# pmic.net
KiCad netlist of a schematic drawn in Altium Designer
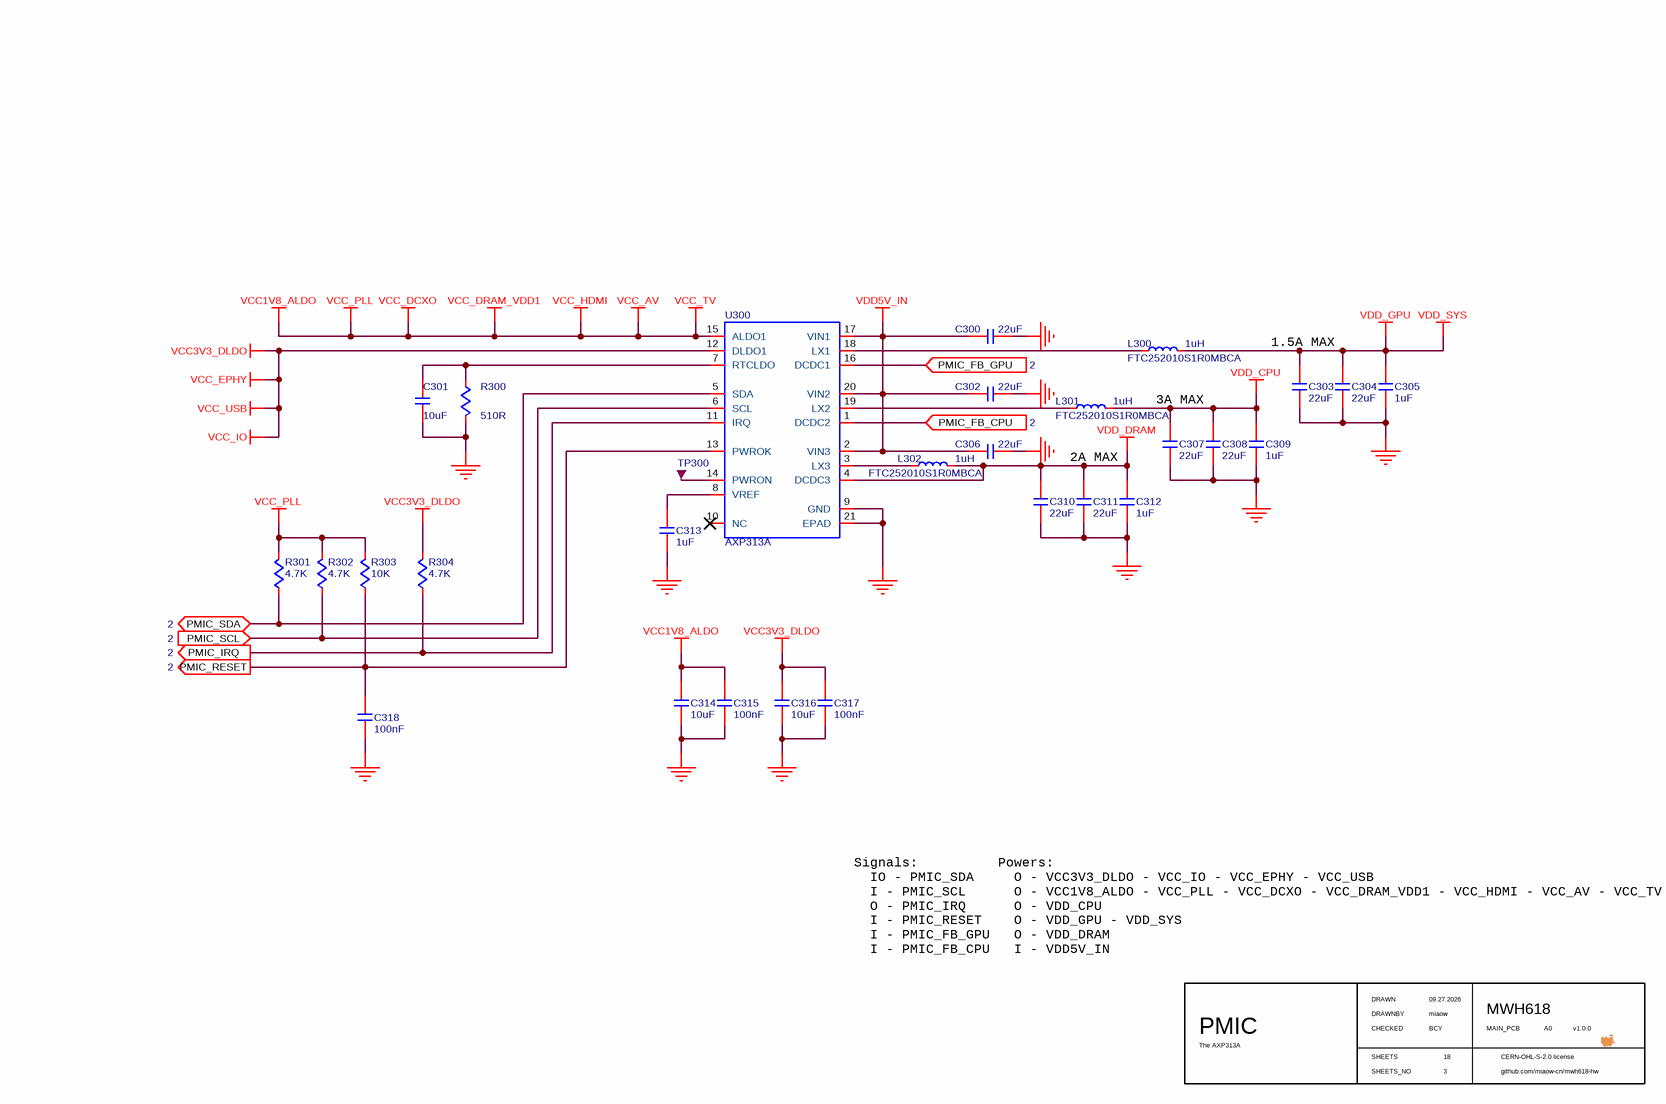
[diagram p0: pmic.schdoc]

(export (version "E")
  (design (tool "Eeschema 10.0.6"))
  (components
    (comp (ref "C300")
      (value "22uF")
      (footprint "mw:C0603")
      (fields (field (name "VOLTAGE") "10V") (field (name "Comment") "C-NOMO"))
      (libsource (lib "mw") (part "C-NOMO"))
    )
    (comp (ref "C301")
      (value "10uF")
      (footprint "mw:C0402")
      (fields (field (name "VOLTAGE") "6.3V") (field (name "Comment") "C-NOMO"))
      (libsource (lib "mw") (part "C-NOMO"))
    )
    (comp (ref "C302")
      (value "22uF")
      (footprint "mw:C0603")
      (fields (field (name "VOLTAGE") "10V") (field (name "Comment") "C-NOMO"))
      (libsource (lib "mw") (part "C-NOMO"))
    )
    (comp (ref "C303")
      (value "22uF")
      (footprint "mw:C0603")
      (fields (field (name "VOLTAGE") "10V") (field (name "Comment") "C-NOMO"))
      (libsource (lib "mw") (part "C-NOMO"))
    )
    (comp (ref "C304")
      (value "22uF")
      (footprint "mw:C0603")
      (fields (field (name "VOLTAGE") "10V") (field (name "Comment") "C-NOMO"))
      (libsource (lib "mw") (part "C-NOMO"))
    )
    (comp (ref "C305")
      (value "1uF")
      (footprint "mw:C0402")
      (fields (field (name "VOLTAGE") "25V") (field (name "Comment") "C-NOMO"))
      (libsource (lib "mw") (part "C-NOMO"))
    )
    (comp (ref "C306")
      (value "22uF")
      (footprint "mw:C0603")
      (fields (field (name "VOLTAGE") "10V") (field (name "Comment") "C-NOMO"))
      (libsource (lib "mw") (part "C-NOMO"))
    )
    (comp (ref "C307")
      (value "22uF")
      (footprint "mw:C0603")
      (fields (field (name "VOLTAGE") "10V") (field (name "Comment") "C-NOMO"))
      (libsource (lib "mw") (part "C-NOMO"))
    )
    (comp (ref "C308")
      (value "22uF")
      (footprint "mw:C0603")
      (fields (field (name "VOLTAGE") "10V") (field (name "Comment") "C-NOMO"))
      (libsource (lib "mw") (part "C-NOMO"))
    )
    (comp (ref "C309")
      (value "1uF")
      (footprint "mw:C0402")
      (fields (field (name "VOLTAGE") "25V") (field (name "Comment") "C-NOMO"))
      (libsource (lib "mw") (part "C-NOMO"))
    )
    (comp (ref "C310")
      (value "22uF")
      (footprint "mw:C0603")
      (fields (field (name "VOLTAGE") "10V") (field (name "Comment") "C-NOMO"))
      (libsource (lib "mw") (part "C-NOMO"))
    )
    (comp (ref "C311")
      (value "22uF")
      (footprint "mw:C0603")
      (fields (field (name "VOLTAGE") "10V") (field (name "Comment") "C-NOMO"))
      (libsource (lib "mw") (part "C-NOMO"))
    )
    (comp (ref "C312")
      (value "1uF")
      (footprint "mw:C0402")
      (fields (field (name "VOLTAGE") "25V") (field (name "Comment") "C-NOMO"))
      (libsource (lib "mw") (part "C-NOMO"))
    )
    (comp (ref "C313")
      (value "1uF")
      (footprint "mw:C0402")
      (fields (field (name "VOLTAGE") "25V") (field (name "Comment") "C-NOMO"))
      (libsource (lib "mw") (part "C-NOMO"))
    )
    (comp (ref "C314")
      (value "10uF")
      (footprint "mw:C0402")
      (fields (field (name "VOLTAGE") "6.3V") (field (name "Comment") "C-NOMO"))
      (libsource (lib "mw") (part "C-NOMO"))
    )
    (comp (ref "C315")
      (value "100nF")
      (footprint "mw:C0402")
      (fields (field (name "VOLTAGE") "50V") (field (name "Comment") "C-NOMO"))
      (libsource (lib "mw") (part "C-NOMO"))
    )
    (comp (ref "C316")
      (value "10uF")
      (footprint "mw:C0402")
      (fields (field (name "VOLTAGE") "6.3V") (field (name "Comment") "C-NOMO"))
      (libsource (lib "mw") (part "C-NOMO"))
    )
    (comp (ref "C317")
      (value "100nF")
      (footprint "mw:C0402")
      (fields (field (name "VOLTAGE") "50V") (field (name "Comment") "C-NOMO"))
      (libsource (lib "mw") (part "C-NOMO"))
    )
    (comp (ref "C318")
      (value "100nF")
      (footprint "mw:C0402")
      (fields (field (name "VOLTAGE") "50V") (field (name "Comment") "C-NOMO"))
      (libsource (lib "mw") (part "C-NOMO"))
    )
    (comp (ref "L300")
      (value "FTC252010S1R0MBCA")
      (footprint "mw:FTC252010")
      (fields (field (name "ALTIUM_VALUE") "1uH") (field (name "PUBLISHER") "Altium Limited"))
      (libsource (lib "mw") (part "L"))
    )
    (comp (ref "L301")
      (value "FTC252010S1R0MBCA")
      (footprint "mw:FTC252010")
      (fields (field (name "ALTIUM_VALUE") "1uH") (field (name "PUBLISHER") "Altium Limited"))
      (libsource (lib "mw") (part "L"))
    )
    (comp (ref "L302")
      (value "FTC252010S1R0MBCA")
      (footprint "mw:FTC252010")
      (fields (field (name "ALTIUM_VALUE") "1uH") (field (name "PUBLISHER") "Altium Limited"))
      (libsource (lib "mw") (part "L"))
    )
    (comp (ref "R300")
      (value "510R")
      (footprint "mw:R0402")
      (fields (field (name "Comment") "R"))
      (libsource (lib "mw") (part "R"))
    )
    (comp (ref "R301")
      (value "4.7K")
      (footprint "mw:R0402")
      (fields (field (name "Comment") "R"))
      (libsource (lib "mw") (part "R"))
    )
    (comp (ref "R302")
      (value "4.7K")
      (footprint "mw:R0402")
      (fields (field (name "Comment") "R"))
      (libsource (lib "mw") (part "R"))
    )
    (comp (ref "R303")
      (value "10K")
      (footprint "mw:R0402")
      (fields (field (name "Comment") "R"))
      (libsource (lib "mw") (part "R"))
    )
    (comp (ref "R304")
      (value "4.7K")
      (footprint "mw:R0402")
      (fields (field (name "Comment") "R"))
      (libsource (lib "mw") (part "R"))
    )
    (comp (ref "TP300") (value "TP") (footprint "mw:TP") (libsource (lib "mw") (part "TP")))
    (comp (ref "U300")
      (value "AXP313A")
      (footprint "mw:AXP313A")
      (description "PMIC")
      (libsource (lib "mw") (part "AXP313A"))
    )
  )
  (nets
    (net (code "1") (name "/PMIC_FB_CPU") (class "Default")
      (node (ref "U300") (pin "1") (pinfunction "DCDC2_1") (pintype "passive"))
    )
    (net (code "2") (name "/PMIC_FB_GPU") (class "Default")
      (node (ref "U300") (pin "16") (pinfunction "DCDC1_16") (pintype "passive"))
    )
    (net (code "3") (name "/PMIC_IRQ") (class "Default")
      (node (ref "R304") (pin "2") (pinfunction "2_2") (pintype "passive"))
      (node (ref "U300") (pin "11") (pinfunction "IRQ_11") (pintype "passive"))
    )
    (net (code "4") (name "/PMIC_RESET") (class "Default")
      (node (ref "C318") (pin "1") (pinfunction "1_1") (pintype "passive"))
      (node (ref "R303") (pin "2") (pinfunction "2_2") (pintype "passive"))
      (node (ref "U300") (pin "13") (pinfunction "PWROK_13") (pintype "passive"))
    )
    (net (code "5") (name "/PMIC_SCL") (class "Default")
      (node (ref "R302") (pin "2") (pinfunction "2_2") (pintype "passive"))
      (node (ref "U300") (pin "6") (pinfunction "SCL_6") (pintype "passive"))
    )
    (net (code "6") (name "/PMIC_SDA") (class "Default")
      (node (ref "R301") (pin "2") (pinfunction "2_2") (pintype "passive"))
      (node (ref "U300") (pin "5") (pinfunction "SDA_5") (pintype "passive"))
    )
    (net (code "7") (name "GND") (class "Default")
      (node (ref "C300") (pin "2") (pinfunction "2_2") (pintype "passive"))
      (node (ref "C301") (pin "2") (pinfunction "2_2") (pintype "passive"))
      (node (ref "C302") (pin "2") (pinfunction "2_2") (pintype "passive"))
      (node (ref "C303") (pin "1") (pinfunction "1_1") (pintype "passive"))
      (node (ref "C304") (pin "1") (pinfunction "1_1") (pintype "passive"))
      (node (ref "C305") (pin "1") (pinfunction "1_1") (pintype "passive"))
      (node (ref "C306") (pin "2") (pinfunction "2_2") (pintype "passive"))
      (node (ref "C307") (pin "1") (pinfunction "1_1") (pintype "passive"))
      (node (ref "C308") (pin "1") (pinfunction "1_1") (pintype "passive"))
      (node (ref "C309") (pin "1") (pinfunction "1_1") (pintype "passive"))
      (node (ref "C310") (pin "1") (pinfunction "1_1") (pintype "passive"))
      (node (ref "C311") (pin "1") (pinfunction "1_1") (pintype "passive"))
      (node (ref "C312") (pin "1") (pinfunction "1_1") (pintype "passive"))
      (node (ref "C313") (pin "2") (pinfunction "2_2") (pintype "passive"))
      (node (ref "C314") (pin "2") (pinfunction "2_2") (pintype "passive"))
      (node (ref "C315") (pin "2") (pinfunction "2_2") (pintype "passive"))
      (node (ref "C316") (pin "2") (pinfunction "2_2") (pintype "passive"))
      (node (ref "C317") (pin "2") (pinfunction "2_2") (pintype "passive"))
      (node (ref "C318") (pin "2") (pinfunction "2_2") (pintype "passive"))
      (node (ref "R300") (pin "1") (pinfunction "1_1") (pintype "passive"))
      (node (ref "U300") (pin "21") (pinfunction "EPAD_21") (pintype "passive"))
      (node (ref "U300") (pin "9") (pinfunction "GND_9") (pintype "passive"))
    )
    (net (code "8") (name "Net-(U300-LX1)") (class "Default")
      (node (ref "L300") (pin "1") (pinfunction "1_1") (pintype "passive"))
      (node (ref "U300") (pin "18") (pinfunction "LX1_18") (pintype "passive"))
    )
    (net (code "9") (name "Net-(U300-LX2)") (class "Default")
      (node (ref "L301") (pin "1") (pinfunction "1_1") (pintype "passive"))
      (node (ref "U300") (pin "19") (pinfunction "LX2_19") (pintype "passive"))
    )
    (net (code "10") (name "Net-(U300-LX3)") (class "Default")
      (node (ref "L302") (pin "1") (pinfunction "1_1") (pintype "passive"))
      (node (ref "U300") (pin "3") (pinfunction "LX3_3") (pintype "passive"))
    )
    (net (code "11") (name "Net-(U300-PWRON)") (class "Default")
      (node (ref "TP300") (pin "0") (pintype "passive"))
      (node (ref "U300") (pin "14") (pinfunction "PWRON_14") (pintype "passive"))
    )
    (net (code "12") (name "Net-(U300-RTCLDO)") (class "Default")
      (node (ref "C301") (pin "1") (pinfunction "1_1") (pintype "passive"))
      (node (ref "R300") (pin "2") (pinfunction "2_2") (pintype "passive"))
      (node (ref "U300") (pin "7") (pinfunction "RTCLDO_7") (pintype "passive"))
    )
    (net (code "13") (name "Net-(U300-VREF)") (class "Default")
      (node (ref "C313") (pin "1") (pinfunction "1_1") (pintype "passive"))
      (node (ref "U300") (pin "8") (pinfunction "VREF_8") (pintype "passive"))
    )
    (net (code "14") (name "VCC1V8_ALDO") (class "Default")
      (node (ref "C314") (pin "1") (pinfunction "1_1") (pintype "passive"))
      (node (ref "C315") (pin "1") (pinfunction "1_1") (pintype "passive"))
      (node (ref "R301") (pin "1") (pinfunction "1_1") (pintype "passive"))
      (node (ref "R302") (pin "1") (pinfunction "1_1") (pintype "passive"))
      (node (ref "R303") (pin "1") (pinfunction "1_1") (pintype "passive"))
      (node (ref "U300") (pin "15") (pinfunction "ALDO1_15") (pintype "passive"))
    )
    (net (code "15") (name "VCC3V3_DLDO") (class "Default")
      (node (ref "C316") (pin "1") (pinfunction "1_1") (pintype "passive"))
      (node (ref "C317") (pin "1") (pinfunction "1_1") (pintype "passive"))
      (node (ref "R304") (pin "1") (pinfunction "1_1") (pintype "passive"))
      (node (ref "U300") (pin "12") (pinfunction "DLDO1_12") (pintype "passive"))
    )
    (net (code "16") (name "VDD5V_IN") (class "Default")
      (node (ref "C300") (pin "1") (pinfunction "1_1") (pintype "passive"))
      (node (ref "C302") (pin "1") (pinfunction "1_1") (pintype "passive"))
      (node (ref "C306") (pin "1") (pinfunction "1_1") (pintype "passive"))
      (node (ref "U300") (pin "17") (pinfunction "VIN1_17") (pintype "passive"))
      (node (ref "U300") (pin "2") (pinfunction "VIN3_2") (pintype "passive"))
      (node (ref "U300") (pin "20") (pinfunction "VIN2_20") (pintype "passive"))
    )
    (net (code "17") (name "VDD_CPU") (class "Default")
      (node (ref "C307") (pin "2") (pinfunction "2_2") (pintype "passive"))
      (node (ref "C308") (pin "2") (pinfunction "2_2") (pintype "passive"))
      (node (ref "C309") (pin "2") (pinfunction "2_2") (pintype "passive"))
      (node (ref "L301") (pin "2") (pinfunction "2_2") (pintype "passive"))
    )
    (net (code "18") (name "VDD_DRAM") (class "Default")
      (node (ref "C310") (pin "2") (pinfunction "2_2") (pintype "passive"))
      (node (ref "C311") (pin "2") (pinfunction "2_2") (pintype "passive"))
      (node (ref "C312") (pin "2") (pinfunction "2_2") (pintype "passive"))
      (node (ref "L302") (pin "2") (pinfunction "2_2") (pintype "passive"))
      (node (ref "U300") (pin "4") (pinfunction "DCDC3_4") (pintype "passive"))
    )
    (net (code "19") (name "VDD_GPU") (class "Default")
      (node (ref "C303") (pin "2") (pinfunction "2_2") (pintype "passive"))
      (node (ref "C304") (pin "2") (pinfunction "2_2") (pintype "passive"))
      (node (ref "C305") (pin "2") (pinfunction "2_2") (pintype "passive"))
      (node (ref "L300") (pin "2") (pinfunction "2_2") (pintype "passive"))
    )
    (net (code "20") (name "unconnected-(U300-NC-Pad10)") (class "Default")
      (node (ref "U300") (pin "10") (pinfunction "NC_10") (pintype "passive+no_connect"))
    )
  )
)
